# esp32_lora_gateway.net
KiCad netlist of a schematic drawn in EAGLE
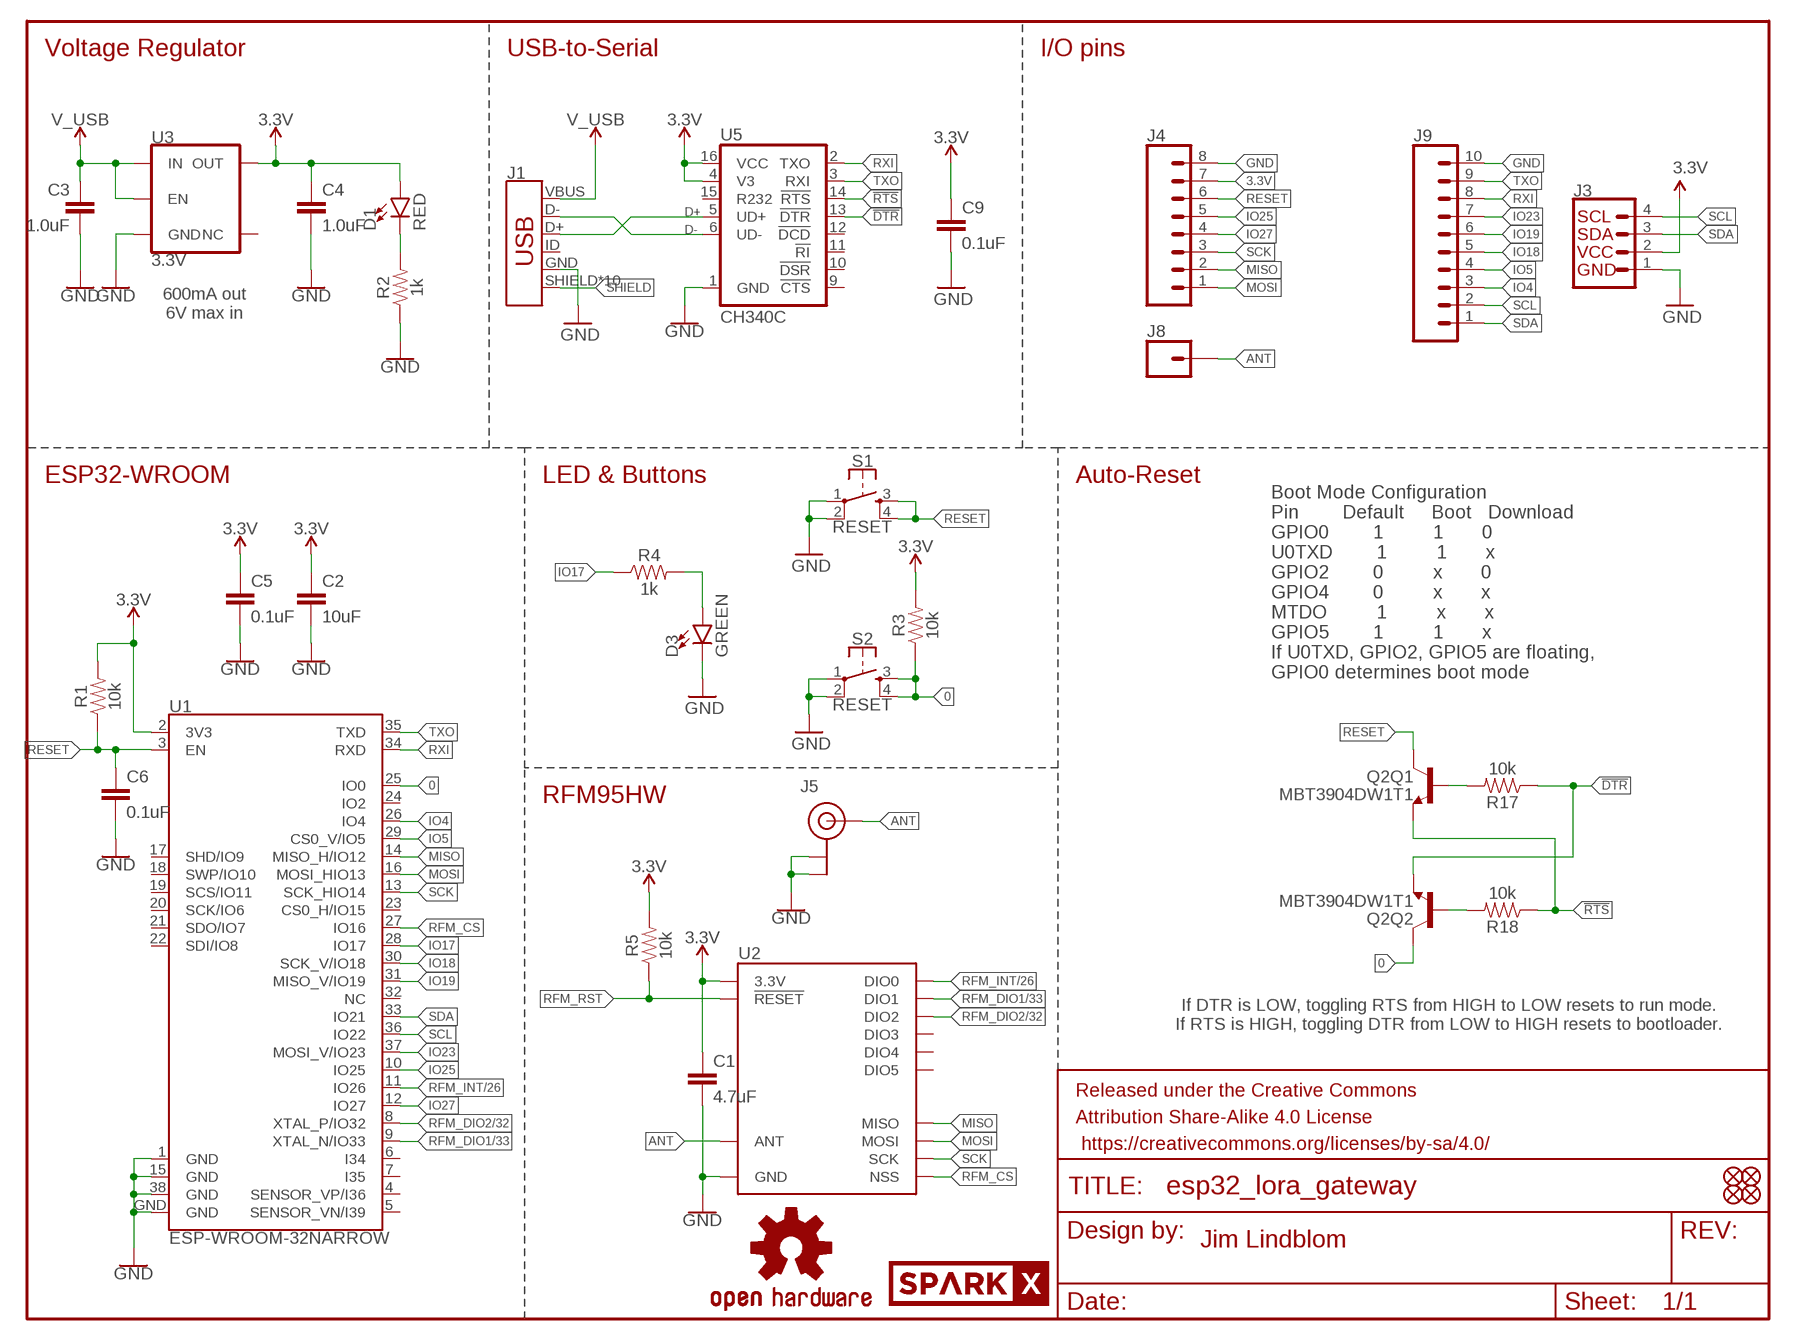
[diagram p0: schematic, sheet 1]

(export (version "E")
  (design (tool "Eeschema 10.0.6"))
  (components
    (comp (ref "C1")
      (value "4.7uF")
      (footprint "eagle-import:0603")
      (libsource (lib "eagle-import") (part "4.7UF-0603-6.3V-(10%)"))
    )
    (comp (ref "C2")
      (value "10uF")
      (footprint "eagle-import:0603")
      (libsource (lib "eagle-import") (part "10UF-0603-6.3V-20%"))
    )
    (comp (ref "C3")
      (value "1.0uF")
      (footprint "eagle-import:0603")
      (libsource (lib "eagle-import") (part "1.0UF-0603-16V-10%"))
    )
    (comp (ref "C4")
      (value "1.0uF")
      (footprint "eagle-import:0603")
      (libsource (lib "eagle-import") (part "1.0UF-0603-16V-10%"))
    )
    (comp (ref "C5")
      (value "0.1uF")
      (footprint "eagle-import:0603")
      (libsource (lib "eagle-import") (part "0.1UF-0603-25V-(+80/-20%)"))
    )
    (comp (ref "C6")
      (value "0.1uF")
      (footprint "eagle-import:0603")
      (libsource (lib "eagle-import") (part "0.1UF-0603-25V-(+80/-20%)"))
    )
    (comp (ref "C9")
      (value "0.1uF")
      (footprint "eagle-import:0603-CAP")
      (libsource (lib "eagle-import") (part "0.1UF-25V(+80/-20%)(0603)"))
    )
    (comp (ref "D1")
      (value "RED")
      (footprint "eagle-import:LED-0603")
      (libsource (lib "eagle-import") (part "LED-RED0603"))
    )
    (comp (ref "D3")
      (value "GREEN")
      (footprint "eagle-import:LED-0603")
      (libsource (lib "eagle-import") (part "LED-GREEN0603"))
    )
    (comp (ref "FD1")
      (value "FIDUCIALUFIDUCIAL")
      (footprint "eagle-import:FIDUCIAL-MICRO")
      (libsource (lib "eagle-import") (part "FIDUCIALUFIDUCIAL"))
    )
    (comp (ref "FD2")
      (value "FIDUCIALUFIDUCIAL")
      (footprint "eagle-import:FIDUCIAL-MICRO")
      (libsource (lib "eagle-import") (part "FIDUCIALUFIDUCIAL"))
    )
    (comp (ref "FD3")
      (value "FIDUCIALUFIDUCIAL")
      (footprint "eagle-import:FIDUCIAL-MICRO")
      (libsource (lib "eagle-import") (part "FIDUCIALUFIDUCIAL"))
    )
    (comp (ref "FD4")
      (value "FIDUCIALUFIDUCIAL")
      (footprint "eagle-import:FIDUCIAL-MICRO")
      (libsource (lib "eagle-import") (part "FIDUCIALUFIDUCIAL"))
    )
    (comp (ref "FRAME1")
      (value "FRAME-LETTER")
      (footprint "eagle-import:CREATIVE_COMMONS")
      (libsource (lib "eagle-import") (part "FRAME-LETTER"))
    )
    (comp (ref "J1")
      (value "USB_MICRO-B_HALF_PTH_MILL")
      (footprint "eagle-import:USB-MICROB-PTH-MILL")
      (libsource (lib "eagle-import") (part "USB_MICRO-B_HALF_PTH_MILL"))
    )
    (comp (ref "J3")
      (value "QWIIC_CONNECTORJS-1MM")
      (footprint "eagle-import:1X04_1MM_RA")
      (libsource (lib "eagle-import") (part "QWIIC_CONNECTORJS-1MM"))
    )
    (comp (ref "J4")
      (value "CONN_08NO_SILK_FEMALE_PTH")
      (footprint "eagle-import:1X08_NO_SILK")
      (libsource (lib "eagle-import") (part "CONN_08NO_SILK_FEMALE_PTH"))
    )
    (comp (ref "J5")
      (value "U.FL")
      (footprint "eagle-import:U.FL")
      (libsource (lib "eagle-import") (part "U.FL"))
    )
    (comp (ref "J8")
      (value "CONN_01PTH_NO_SILK_YES_STOP")
      (footprint "eagle-import:1X01_NO_SILK")
      (libsource (lib "eagle-import") (part "CONN_01PTH_NO_SILK_YES_STOP"))
    )
    (comp (ref "J9")
      (value "CONN_10NO_SILK_PTH_FEMALE")
      (footprint "eagle-import:1X10_NO_SILK")
      (libsource (lib "eagle-import") (part "CONN_10NO_SILK_PTH_FEMALE"))
    )
    (comp (ref "LOGO1")
      (value "SPARKX-LOGO4")
      (footprint "eagle-import:SPARKX-MEDIUM")
      (libsource (lib "eagle-import") (part "SPARKX-LOGO4"))
    )
    (comp (ref "LOGO2")
      (value "OSHW-LOGOM")
      (footprint "eagle-import:OSHW-LOGO-M")
      (libsource (lib "eagle-import") (part "OSHW-LOGOM"))
    )
    (comp (ref "Q2")
      (value "MBT3904DW1T1")
      (footprint "eagle-import:SC70-6")
      (libsource (lib "eagle-import") (part "MBT3904DW1T1"))
    )
    (comp (ref "R1")
      (value "10k")
      (footprint "eagle-import:0603")
      (libsource (lib "eagle-import") (part "10KOHM-0603-1/10W-1%"))
    )
    (comp (ref "R2")
      (value "1k")
      (footprint "eagle-import:0603")
      (libsource (lib "eagle-import") (part "1KOHM-0603-1/10W-1%"))
    )
    (comp (ref "R3")
      (value "10k")
      (footprint "eagle-import:0603")
      (libsource (lib "eagle-import") (part "10KOHM-0603-1/10W-1%"))
    )
    (comp (ref "R4")
      (value "1k")
      (footprint "eagle-import:0603")
      (libsource (lib "eagle-import") (part "1KOHM-0603-1/10W-1%"))
    )
    (comp (ref "R5")
      (value "10k")
      (footprint "eagle-import:0603")
      (libsource (lib "eagle-import") (part "10KOHM-0603-1/10W-1%"))
    )
    (comp (ref "R17")
      (value "10k")
      (footprint "eagle-import:0603")
      (libsource (lib "eagle-import") (part "10KOHM-0603-1/10W-1%"))
    )
    (comp (ref "R18")
      (value "10k")
      (footprint "eagle-import:0603")
      (libsource (lib "eagle-import") (part "10KOHM-0603-1/10W-1%"))
    )
    (comp (ref "S1")
      (value "RESET")
      (footprint "eagle-import:TACTILE_SWITCH_SMD_4.6X2.8MM")
      (libsource (lib "eagle-import") (part "MOMENTARY-SWITCH-SPST-2-SMD-4.6X2.8MM"))
    )
    (comp (ref "S2")
      (value "RESET")
      (footprint "eagle-import:TACTILE_SWITCH_SMD_4.6X2.8MM")
      (libsource (lib "eagle-import") (part "MOMENTARY-SWITCH-SPST-2-SMD-4.6X2.8MM"))
    )
    (comp (ref "U1")
      (value "ESP-WROOM-32NARROW")
      (footprint "eagle-import:ESP-WROOM-32-NARROW")
      (libsource (lib "eagle-import") (part "ESP-WROOM-32NARROW"))
    )
    (comp (ref "U2")
      (value "RFM96W")
      (footprint "eagle-import:RFM95_96_97_98W")
      (libsource (lib "eagle-import") (part "RFM96W"))
    )
    (comp (ref "U3")
      (value "3.3V")
      (footprint "eagle-import:SOT23-5")
      (libsource (lib "eagle-import") (part "V_REG_AP2112K-3.3V"))
    )
    (comp (ref "U5")
      (value "CH340C")
      (footprint "eagle-import:SO016")
      (libsource (lib "eagle-import") (part "CH340C"))
    )
  )
  (nets
    (net (code "1") (name "/D+") (class "Default")
      (node (ref "J1") (pin "D+") (pinfunction "D+_D+") (pintype "bidirectional"))
      (node (ref "U5") (pin "5") (pinfunction "UD+_5") (pintype "bidirectional"))
    )
    (net (code "2") (name "/D-") (class "Default")
      (node (ref "J1") (pin "D-") (pinfunction "D-_D-") (pintype "bidirectional"))
      (node (ref "U5") (pin "6") (pinfunction "UD-_6") (pintype "bidirectional"))
    )
    (net (code "3") (name "/~{DTR}") (class "Default")
      (node (ref "Q2") (pin "1") (pinfunction "E_1") (pintype "passive"))
      (node (ref "R17") (pin "1") (pinfunction "1_1") (pintype "passive"))
      (node (ref "U5") (pin "13") (pinfunction "~{DTR}_13") (pintype "bidirectional"))
    )
    (net (code "4") (name "/~{RTS}") (class "Default")
      (node (ref "Q2") (pin "4") (pinfunction "E_4") (pintype "passive"))
      (node (ref "R18") (pin "1") (pinfunction "1_1") (pintype "passive"))
      (node (ref "U5") (pin "14") (pinfunction "~{RTS}_14") (pintype "bidirectional"))
    )
    (net (code "5") (name "0") (class "Default")
      (node (ref "Q2") (pin "6") (pinfunction "C_6") (pintype "passive"))
      (node (ref "R3") (pin "1") (pinfunction "1_1") (pintype "passive"))
      (node (ref "S2") (pin "3") (pinfunction "3_3") (pintype "passive"))
      (node (ref "S2") (pin "4") (pinfunction "4_4") (pintype "passive"))
      (node (ref "U1") (pin "25") (pinfunction "IO0_25") (pintype "bidirectional"))
    )
    (net (code "6") (name "3.3V") (class "Default")
      (node (ref "C1") (pin "1") (pinfunction "1_1") (pintype "passive"))
      (node (ref "C2") (pin "1") (pinfunction "1_1") (pintype "passive"))
      (node (ref "C4") (pin "1") (pinfunction "1_1") (pintype "passive"))
      (node (ref "C5") (pin "1") (pinfunction "1_1") (pintype "passive"))
      (node (ref "C9") (pin "1") (pinfunction "1_1") (pintype "passive"))
      (node (ref "D1") (pin "A") (pinfunction "A_A") (pintype "passive"))
      (node (ref "J3") (pin "2") (pinfunction "2_2") (pintype "power_in"))
      (node (ref "J4") (pin "7") (pinfunction "7_7") (pintype "passive"))
      (node (ref "R1") (pin "2") (pinfunction "2_2") (pintype "passive"))
      (node (ref "R3") (pin "2") (pinfunction "2_2") (pintype "passive"))
      (node (ref "R5") (pin "2") (pinfunction "2_2") (pintype "passive"))
      (node (ref "U1") (pin "2") (pinfunction "3V3_2") (pintype "bidirectional"))
      (node (ref "U2") (pin "3.3V") (pinfunction "3.3V_3.3V") (pintype "bidirectional"))
      (node (ref "U3") (pin "5") (pinfunction "OUT_5") (pintype "passive"))
      (node (ref "U5") (pin "16") (pinfunction "VCC_16") (pintype "bidirectional"))
      (node (ref "U5") (pin "4") (pinfunction "V3_4") (pintype "bidirectional"))
    )
    (net (code "7") (name "ANT") (class "Default")
      (node (ref "J5") (pin "FEED") (pinfunction "SIGNAL_FEED") (pintype "bidirectional"))
      (node (ref "J8") (pin "1") (pinfunction "1_1") (pintype "passive"))
      (node (ref "U2") (pin "ANT") (pinfunction "ANT_ANT") (pintype "bidirectional"))
    )
    (net (code "8") (name "GND") (class "Default")
      (node (ref "C1") (pin "2") (pinfunction "2_2") (pintype "passive"))
      (node (ref "C2") (pin "2") (pinfunction "2_2") (pintype "passive"))
      (node (ref "C3") (pin "2") (pinfunction "2_2") (pintype "passive"))
      (node (ref "C4") (pin "2") (pinfunction "2_2") (pintype "passive"))
      (node (ref "C5") (pin "2") (pinfunction "2_2") (pintype "passive"))
      (node (ref "C6") (pin "2") (pinfunction "2_2") (pintype "passive"))
      (node (ref "C9") (pin "2") (pinfunction "2_2") (pintype "passive"))
      (node (ref "D3") (pin "C") (pinfunction "C_C") (pintype "passive"))
      (node (ref "J1") (pin "GND") (pinfunction "GND_GND") (pintype "power_in"))
      (node (ref "J3") (pin "1") (pinfunction "1_1") (pintype "power_in"))
      (node (ref "J4") (pin "8") (pinfunction "8_8") (pintype "passive"))
      (node (ref "J5") (pin "1") (pinfunction "GND_1") (pintype "bidirectional"))
      (node (ref "J5") (pin "2") (pinfunction "GND_2") (pintype "bidirectional"))
      (node (ref "J9") (pin "10") (pinfunction "10_10") (pintype "passive"))
      (node (ref "R2") (pin "1") (pinfunction "1_1") (pintype "passive"))
      (node (ref "S1") (pin "1") (pinfunction "1_1") (pintype "passive"))
      (node (ref "S1") (pin "2") (pinfunction "2_2") (pintype "passive"))
      (node (ref "S2") (pin "1") (pinfunction "1_1") (pintype "passive"))
      (node (ref "S2") (pin "2") (pinfunction "2_2") (pintype "passive"))
      (node (ref "U1") (pin "1") (pinfunction "GND_1") (pintype "bidirectional"))
      (node (ref "U1") (pin "15") (pinfunction "GND_15") (pintype "bidirectional"))
      (node (ref "U1") (pin "38") (pinfunction "GND_38") (pintype "bidirectional"))
      (node (ref "U1") (pin "GND") (pinfunction "GND_GND") (pintype "bidirectional"))
      (node (ref "U2") (pin "GND@1") (pinfunction "GND_GND@1") (pintype "bidirectional"))
      (node (ref "U2") (pin "GND@2") (pinfunction "GND_GND@2") (pintype "bidirectional"))
      (node (ref "U2") (pin "GND@3") (pinfunction "GND_GND@3") (pintype "bidirectional"))
      (node (ref "U3") (pin "2") (pinfunction "GND_2") (pintype "input"))
      (node (ref "U5") (pin "1") (pinfunction "GND_1") (pintype "bidirectional"))
    )
    (net (code "9") (name "IO4") (class "Default")
      (node (ref "J9") (pin "3") (pinfunction "3_3") (pintype "passive"))
      (node (ref "U1") (pin "26") (pinfunction "IO4_26") (pintype "bidirectional"))
    )
    (net (code "10") (name "IO5") (class "Default")
      (node (ref "J9") (pin "4") (pinfunction "4_4") (pintype "passive"))
      (node (ref "U1") (pin "29") (pinfunction "CS0_V/IO5_29") (pintype "bidirectional"))
    )
    (net (code "11") (name "IO17") (class "Default")
      (node (ref "R4") (pin "1") (pinfunction "1_1") (pintype "passive"))
      (node (ref "U1") (pin "28") (pinfunction "IO17_28") (pintype "bidirectional"))
    )
    (net (code "12") (name "IO18") (class "Default")
      (node (ref "J9") (pin "5") (pinfunction "5_5") (pintype "passive"))
      (node (ref "U1") (pin "30") (pinfunction "SCK_V/IO18_30") (pintype "bidirectional"))
    )
    (net (code "13") (name "IO19") (class "Default")
      (node (ref "J9") (pin "6") (pinfunction "6_6") (pintype "passive"))
      (node (ref "U1") (pin "31") (pinfunction "MISO_V/IO19_31") (pintype "bidirectional"))
    )
    (net (code "14") (name "IO23") (class "Default")
      (node (ref "J9") (pin "7") (pinfunction "7_7") (pintype "passive"))
      (node (ref "U1") (pin "37") (pinfunction "MOSI_V/IO23_37") (pintype "bidirectional"))
    )
    (net (code "15") (name "IO25") (class "Default")
      (node (ref "J4") (pin "5") (pinfunction "5_5") (pintype "passive"))
      (node (ref "U1") (pin "10") (pinfunction "IO25_10") (pintype "bidirectional"))
    )
    (net (code "16") (name "IO27") (class "Default")
      (node (ref "J4") (pin "4") (pinfunction "4_4") (pintype "passive"))
      (node (ref "U1") (pin "12") (pinfunction "IO27_12") (pintype "bidirectional"))
    )
    (net (code "17") (name "MISO") (class "Default")
      (node (ref "J4") (pin "2") (pinfunction "2_2") (pintype "passive"))
      (node (ref "U1") (pin "14") (pinfunction "MISO_H/IO12_14") (pintype "bidirectional"))
      (node (ref "U2") (pin "MISO") (pinfunction "MISO_MISO") (pintype "bidirectional"))
    )
    (net (code "18") (name "MOSI") (class "Default")
      (node (ref "J4") (pin "1") (pinfunction "1_1") (pintype "passive"))
      (node (ref "U1") (pin "16") (pinfunction "MOSI_HIO13_16") (pintype "bidirectional"))
      (node (ref "U2") (pin "MOSI") (pinfunction "MOSI_MOSI") (pintype "bidirectional"))
    )
    (net (code "19") (name "Net-(D1-PadC)") (class "Default")
      (node (ref "D1") (pin "C") (pinfunction "C_C") (pintype "passive"))
      (node (ref "R2") (pin "2") (pinfunction "2_2") (pintype "passive"))
    )
    (net (code "20") (name "Net-(D3-PadA)") (class "Default")
      (node (ref "D3") (pin "A") (pinfunction "A_A") (pintype "passive"))
      (node (ref "R4") (pin "2") (pinfunction "2_2") (pintype "passive"))
    )
    (net (code "21") (name "Net-(Q2A-B)") (class "Default")
      (node (ref "Q2") (pin "5") (pinfunction "B_5") (pintype "passive"))
      (node (ref "R17") (pin "2") (pinfunction "2_2") (pintype "passive"))
    )
    (net (code "22") (name "Net-(Q2B-B)") (class "Default")
      (node (ref "Q2") (pin "2") (pinfunction "B_2") (pintype "passive"))
      (node (ref "R18") (pin "2") (pinfunction "2_2") (pintype "passive"))
    )
    (net (code "23") (name "RESET") (class "Default")
      (node (ref "C6") (pin "1") (pinfunction "1_1") (pintype "passive"))
      (node (ref "J4") (pin "6") (pinfunction "6_6") (pintype "passive"))
      (node (ref "Q2") (pin "3") (pinfunction "C_3") (pintype "passive"))
      (node (ref "R1") (pin "1") (pinfunction "1_1") (pintype "passive"))
      (node (ref "S1") (pin "3") (pinfunction "3_3") (pintype "passive"))
      (node (ref "S1") (pin "4") (pinfunction "4_4") (pintype "passive"))
      (node (ref "U1") (pin "3") (pinfunction "EN_3") (pintype "bidirectional"))
    )
    (net (code "24") (name "RFM_CS") (class "Default")
      (node (ref "U1") (pin "27") (pinfunction "IO16_27") (pintype "bidirectional"))
      (node (ref "U2") (pin "NSS") (pinfunction "NSS_NSS") (pintype "bidirectional"))
    )
    (net (code "25") (name "RFM_DIO1{slash}33") (class "Default")
      (node (ref "U1") (pin "9") (pinfunction "XTAL_N/IO33_9") (pintype "bidirectional"))
      (node (ref "U2") (pin "DIO1") (pinfunction "DIO1_DIO1") (pintype "bidirectional"))
    )
    (net (code "26") (name "RFM_DIO2{slash}32") (class "Default")
      (node (ref "U1") (pin "8") (pinfunction "XTAL_P/IO32_8") (pintype "bidirectional"))
      (node (ref "U2") (pin "DIO2") (pinfunction "DIO2_DIO2") (pintype "bidirectional"))
    )
    (net (code "27") (name "RFM_INT{slash}26") (class "Default")
      (node (ref "U1") (pin "11") (pinfunction "IO26_11") (pintype "bidirectional"))
      (node (ref "U2") (pin "DIO0") (pinfunction "DIO0_DIO0") (pintype "bidirectional"))
    )
    (net (code "28") (name "RFM_RST") (class "Default")
      (node (ref "R5") (pin "1") (pinfunction "1_1") (pintype "passive"))
      (node (ref "U2") (pin "!RESET") (pinfunction "~{RESET}_!RESET") (pintype "bidirectional"))
    )
    (net (code "29") (name "RXI") (class "Default")
      (node (ref "J9") (pin "8") (pinfunction "8_8") (pintype "passive"))
      (node (ref "U1") (pin "34") (pinfunction "RXD_34") (pintype "bidirectional"))
      (node (ref "U5") (pin "2") (pinfunction "TXO_2") (pintype "bidirectional"))
    )
    (net (code "30") (name "SCK") (class "Default")
      (node (ref "J4") (pin "3") (pinfunction "3_3") (pintype "passive"))
      (node (ref "U1") (pin "13") (pinfunction "SCK_HIO14_13") (pintype "bidirectional"))
      (node (ref "U2") (pin "SCK") (pinfunction "SCK_SCK") (pintype "bidirectional"))
    )
    (net (code "31") (name "SCL") (class "Default")
      (node (ref "J3") (pin "4") (pinfunction "4_4") (pintype "passive"))
      (node (ref "J9") (pin "2") (pinfunction "2_2") (pintype "passive"))
      (node (ref "U1") (pin "36") (pinfunction "IO22_36") (pintype "bidirectional"))
    )
    (net (code "32") (name "SDA") (class "Default")
      (node (ref "J3") (pin "3") (pinfunction "3_3") (pintype "passive"))
      (node (ref "J9") (pin "1") (pinfunction "1_1") (pintype "passive"))
      (node (ref "U1") (pin "33") (pinfunction "IO21_33") (pintype "bidirectional"))
    )
    (net (code "33") (name "SHIELD") (class "Default")
      (node (ref "J1") (pin "SHIELD") (pinfunction "SHIELD_SHIELD") (pintype "bidirectional"))
      (node (ref "J1") (pin "SHIELD10") (pinfunction "SHIELD_SHIELD10") (pintype "bidirectional"))
      (node (ref "J1") (pin "SHIELD2") (pinfunction "SHIELD_SHIELD2") (pintype "bidirectional"))
      (node (ref "J1") (pin "SHIELD3") (pinfunction "SHIELD_SHIELD3") (pintype "bidirectional"))
      (node (ref "J1") (pin "SHIELD4") (pinfunction "SHIELD_SHIELD4") (pintype "bidirectional"))
      (node (ref "J1") (pin "SHIELD5") (pinfunction "SHIELD_SHIELD5") (pintype "bidirectional"))
      (node (ref "J1") (pin "SHIELD6") (pinfunction "SHIELD_SHIELD6") (pintype "bidirectional"))
      (node (ref "J1") (pin "SHIELD7") (pinfunction "SHIELD_SHIELD7") (pintype "bidirectional"))
      (node (ref "J1") (pin "SHIELD8") (pinfunction "SHIELD_SHIELD8") (pintype "bidirectional"))
      (node (ref "J1") (pin "SHIELD9") (pinfunction "SHIELD_SHIELD9") (pintype "bidirectional"))
    )
    (net (code "34") (name "TXO") (class "Default")
      (node (ref "J9") (pin "9") (pinfunction "9_9") (pintype "passive"))
      (node (ref "U1") (pin "35") (pinfunction "TXD_35") (pintype "bidirectional"))
      (node (ref "U5") (pin "3") (pinfunction "RXI_3") (pintype "bidirectional"))
    )
    (net (code "35") (name "V_USB") (class "Default")
      (node (ref "C3") (pin "1") (pinfunction "1_1") (pintype "passive"))
      (node (ref "J1") (pin "VBUS") (pinfunction "VBUS_VBUS") (pintype "power_in"))
      (node (ref "U3") (pin "1") (pinfunction "IN_1") (pintype "input"))
      (node (ref "U3") (pin "3") (pinfunction "EN_3") (pintype "input"))
    )
    (net (code "36") (name "unconnected-(J1-PadID)") (class "Default")
      (node (ref "J1") (pin "ID") (pinfunction "ID_ID") (pintype "bidirectional"))
    )
    (net (code "37") (name "unconnected-(U1-CS0_H{slash}IO15-Pad23)") (class "Default")
      (node (ref "U1") (pin "23") (pinfunction "CS0_H/IO15_23") (pintype "bidirectional"))
    )
    (net (code "38") (name "unconnected-(U1-I34-Pad6)") (class "Default")
      (node (ref "U1") (pin "6") (pinfunction "I34_6") (pintype "bidirectional"))
    )
    (net (code "39") (name "unconnected-(U1-I35-Pad7)") (class "Default")
      (node (ref "U1") (pin "7") (pinfunction "I35_7") (pintype "bidirectional"))
    )
    (net (code "40") (name "unconnected-(U1-IO2-Pad24)") (class "Default")
      (node (ref "U1") (pin "24") (pinfunction "IO2_24") (pintype "bidirectional"))
    )
    (net (code "41") (name "unconnected-(U1-NC-Pad32)") (class "Default")
      (node (ref "U1") (pin "32") (pinfunction "NC_32") (pintype "bidirectional"))
    )
    (net (code "42") (name "unconnected-(U1-SCK{slash}IO6-Pad20)") (class "Default")
      (node (ref "U1") (pin "20") (pinfunction "SCK/IO6_20") (pintype "bidirectional"))
    )
    (net (code "43") (name "unconnected-(U1-SCS{slash}IO11-Pad19)") (class "Default")
      (node (ref "U1") (pin "19") (pinfunction "SCS/IO11_19") (pintype "bidirectional"))
    )
    (net (code "44") (name "unconnected-(U1-SDI{slash}IO8-Pad22)") (class "Default")
      (node (ref "U1") (pin "22") (pinfunction "SDI/IO8_22") (pintype "bidirectional"))
    )
    (net (code "45") (name "unconnected-(U1-SDO{slash}IO7-Pad21)") (class "Default")
      (node (ref "U1") (pin "21") (pinfunction "SDO/IO7_21") (pintype "bidirectional"))
    )
    (net (code "46") (name "unconnected-(U1-SENSOR_VN{slash}I39-Pad5)") (class "Default")
      (node (ref "U1") (pin "5") (pinfunction "SENSOR_VN/I39_5") (pintype "bidirectional"))
    )
    (net (code "47") (name "unconnected-(U1-SENSOR_VP{slash}I36-Pad4)") (class "Default")
      (node (ref "U1") (pin "4") (pinfunction "SENSOR_VP/I36_4") (pintype "bidirectional"))
    )
    (net (code "48") (name "unconnected-(U1-SHD{slash}IO9-Pad17)") (class "Default")
      (node (ref "U1") (pin "17") (pinfunction "SHD/IO9_17") (pintype "bidirectional"))
    )
    (net (code "49") (name "unconnected-(U1-SWP{slash}IO10-Pad18)") (class "Default")
      (node (ref "U1") (pin "18") (pinfunction "SWP/IO10_18") (pintype "bidirectional"))
    )
    (net (code "50") (name "unconnected-(U2-PadDIO3)") (class "Default")
      (node (ref "U2") (pin "DIO3") (pinfunction "DIO3_DIO3") (pintype "bidirectional"))
    )
    (net (code "51") (name "unconnected-(U2-PadDIO4)") (class "Default")
      (node (ref "U2") (pin "DIO4") (pinfunction "DIO4_DIO4") (pintype "bidirectional"))
    )
    (net (code "52") (name "unconnected-(U2-PadDIO5)") (class "Default")
      (node (ref "U2") (pin "DIO5") (pinfunction "DIO5_DIO5") (pintype "bidirectional"))
    )
    (net (code "53") (name "unconnected-(U3-NC-Pad4)") (class "Default")
      (node (ref "U3") (pin "4") (pinfunction "NC_4") (pintype "no_connect"))
    )
    (net (code "54") (name "unconnected-(U5-R232-Pad15)") (class "Default")
      (node (ref "U5") (pin "15") (pinfunction "R232_15") (pintype "bidirectional"))
    )
    (net (code "55") (name "unconnected-(U5-~{CTS}-Pad9)") (class "Default")
      (node (ref "U5") (pin "9") (pinfunction "~{CTS}_9") (pintype "bidirectional"))
    )
    (net (code "56") (name "unconnected-(U5-~{DCD}-Pad12)") (class "Default")
      (node (ref "U5") (pin "12") (pinfunction "~{DCD}_12") (pintype "bidirectional"))
    )
    (net (code "57") (name "unconnected-(U5-~{DSR}-Pad10)") (class "Default")
      (node (ref "U5") (pin "10") (pinfunction "~{DSR}_10") (pintype "bidirectional"))
    )
    (net (code "58") (name "unconnected-(U5-~{RI}-Pad11)") (class "Default")
      (node (ref "U5") (pin "11") (pinfunction "~{RI}_11") (pintype "bidirectional"))
    )
  )
)
